# Transimpedance_amplifier.net
KiCad netlist of a schematic drawn in EAGLE
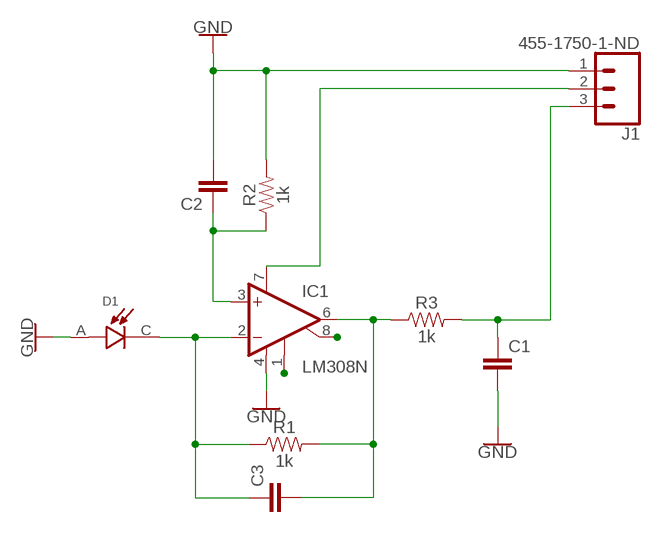
[diagram p0: schematic, sheet 1]

(export (version "E")
  (design (tool "Eeschema 10.0.6"))
  (components
    (comp (ref "C1")
      (value "C2.5/2")
      (footprint "eagle-import:C2.5-2")
      (libsource (lib "eagle-import") (part "C2.5/2"))
    )
    (comp (ref "C2")
      (value "C2.5/2")
      (footprint "eagle-import:C2.5-2")
      (libsource (lib "eagle-import") (part "C2.5/2"))
    )
    (comp (ref "C3")
      (value "C2.5/2")
      (footprint "eagle-import:C2.5-2")
      (libsource (lib "eagle-import") (part "C2.5/2"))
    )
    (comp (ref "D1")
      (value "BPW_21")
      (footprint "eagle-import:TO254P950H570-2")
      (fields (field (name "MF") "OSRAM Opto") (field (name "MP") "BPW 21"))
      (libsource (lib "eagle-import") (part "BPW_21"))
    )
    (comp (ref "IC1")
      (value "LM308N")
      (footprint "eagle-import:DIL08")
      (libsource (lib "eagle-import") (part "LM308N"))
    )
    (comp (ref "J1")
      (value "455-1750-1-ND")
      (footprint "eagle-import:1X03")
      (libsource (lib "eagle-import") (part "CONN_03"))
    )
    (comp (ref "R1")
      (value "1k")
      (footprint "eagle-import:AXIAL-0.3")
      (libsource (lib "eagle-import") (part "1KOHM-HORIZ-1/4W-5%"))
    )
    (comp (ref "R2")
      (value "1k")
      (footprint "eagle-import:AXIAL-0.3")
      (libsource (lib "eagle-import") (part "1KOHM-HORIZ-1/4W-5%"))
    )
    (comp (ref "R3")
      (value "1k")
      (footprint "eagle-import:AXIAL-0.3")
      (libsource (lib "eagle-import") (part "1KOHM-HORIZ-1/4W-1%"))
    )
  )
  (nets
    (net (code "1") (name "GND") (class "Default")
      (node (ref "C1") (pin "2") (pinfunction "2_2") (pintype "passive"))
      (node (ref "C2") (pin "2") (pinfunction "2_2") (pintype "passive"))
      (node (ref "D1") (pin "A") (pinfunction "A_A") (pintype "passive"))
      (node (ref "IC1") (pin "4") (pinfunction "V-_4") (pintype "power_in"))
      (node (ref "J1") (pin "1") (pinfunction "1_1") (pintype "passive"))
      (node (ref "R2") (pin "P$2") (pinfunction "2_P$2") (pintype "passive"))
    )
    (net (code "2") (name "Net-(IC1-+IN)") (class "Default")
      (node (ref "C2") (pin "1") (pinfunction "1_1") (pintype "passive"))
      (node (ref "IC1") (pin "3") (pinfunction "+IN_3") (pintype "input"))
      (node (ref "R2") (pin "P$1") (pinfunction "1_P$1") (pintype "passive"))
    )
    (net (code "3") (name "Net-(IC1--IN)") (class "Default")
      (node (ref "C3") (pin "1") (pinfunction "1_1") (pintype "passive"))
      (node (ref "D1") (pin "C") (pinfunction "C_C") (pintype "passive"))
      (node (ref "IC1") (pin "2") (pinfunction "-IN_2") (pintype "input"))
      (node (ref "R1") (pin "P$1") (pinfunction "1_P$1") (pintype "passive"))
    )
    (net (code "4") (name "Net-(IC1-OUT)") (class "Default")
      (node (ref "C3") (pin "2") (pinfunction "2_2") (pintype "passive"))
      (node (ref "IC1") (pin "6") (pinfunction "OUT_6") (pintype "output"))
      (node (ref "R1") (pin "P$2") (pinfunction "2_P$2") (pintype "passive"))
      (node (ref "R3") (pin "P$1") (pinfunction "1_P$1") (pintype "passive"))
    )
    (net (code "5") (name "Net-(IC1-V+)") (class "Default")
      (node (ref "IC1") (pin "7") (pinfunction "V+_7") (pintype "power_in"))
      (node (ref "J1") (pin "2") (pinfunction "2_2") (pintype "passive"))
    )
    (net (code "6") (name "Net-(R3-2)") (class "Default")
      (node (ref "C1") (pin "1") (pinfunction "1_1") (pintype "passive"))
      (node (ref "J1") (pin "3") (pinfunction "3_3") (pintype "passive"))
      (node (ref "R3") (pin "P$2") (pinfunction "2_P$2") (pintype "passive"))
    )
    (net (code "7") (name "unconnected-(IC1-CMP1-Pad1)") (class "Default")
      (node (ref "IC1") (pin "1") (pinfunction "CMP1_1") (pintype "passive"))
    )
    (net (code "8") (name "unconnected-(IC1-CMP2-Pad8)") (class "Default")
      (node (ref "IC1") (pin "8") (pinfunction "CMP2_8") (pintype "passive"))
    )
  )
)
